# TOD.net
KiCad netlist of a schematic drawn in Altium Designer
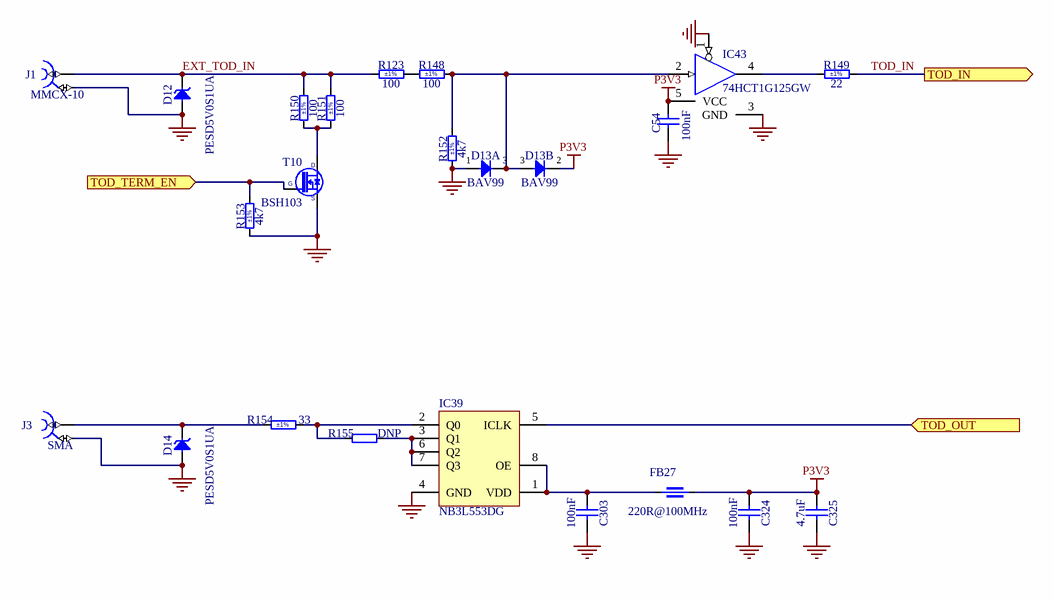
[diagram p0: TOD.SchDoc]

(export (version "E")
  (design (tool "Eeschema 10.0.6"))
  (components
    (comp (ref "C54")
      (value "100nF")
      (footprint "CAPC0603X33N")
      (description "Non-polarised capacitor")
      (fields
        (field (name "PART NUMBER") "CC0201_100NF_6.3V_10%_X5R")
        (field (name "VOLTAGE") "6.3V")
        (field (name "AUTHOR") "CERN DEM JLC")
      )
      (libsource (lib "Capacitors") (part "Capacitor - non polarized"))
    )
    (comp (ref "C303")
      (value "100nF")
      (footprint "CAPC0603X33N")
      (description "Non-polarised capacitor")
      (fields
        (field (name "PART NUMBER") "CC0201_100NF_6.3V_10%_X5R")
        (field (name "VOLTAGE") "6.3V")
        (field (name "AUTHOR") "CERN DEM JLC")
      )
      (libsource (lib "Capacitors") (part "Capacitor - non polarized"))
    )
    (comp (ref "C324")
      (value "100nF")
      (footprint "CAPC0603X33N")
      (description "Non-polarised capacitor")
      (fields
        (field (name "PART NUMBER") "CC0201_100NF_6.3V_10%_X5R")
        (field (name "VOLTAGE") "6.3V")
        (field (name "AUTHOR") "CERN DEM JLC")
      )
      (libsource (lib "Capacitors") (part "Capacitor - non polarized"))
    )
    (comp (ref "C325")
      (value "4.7uF")
      (footprint "CAPC1005X55N")
      (description "Non-polarised capacitor")
      (fields
        (field (name "PART NUMBER") "CC0402_4.7UF_6.3V_20%_X5R")
        (field (name "VOLTAGE") "6.3V")
        (field (name "AUTHOR") "CERN DEM JLC")
      )
      (libsource (lib "Capacitors") (part "Capacitor - non polarized"))
    )
    (comp (ref "D12")
      (value "PESD5V0S1UA")
      (footprint "SOD2512X110N")
      (description "Transient Voltage Suppressor Diode (Uni-Directional)")
      (fields
        (field (name "VOLTAGE") "5V")
        (field (name "POWER") "890W")
        (field (name "AUTHOR") "CERN DEM JLC")
      )
      (libsource (lib "ICs And Semiconductors") (part "Diode TVS Uni-Directional"))
    )
    (comp (ref "D13")
      (value "BAV99")
      (footprint "SOT95P240X110-3N")
      (description "Serial Diode")
      (fields
        (field (name "VOLTAGE") "70V")
        (field (name "POWER") "350mW")
        (field (name "AUTHOR") "CERN DEM JLC")
      )
      (libsource (lib "ICs And Semiconductors") (part "Diode x2 A1C3_A3C2"))
    )
    (comp (ref "D14")
      (value "PESD5V0S1UA")
      (footprint "SOD2512X110N")
      (description "Transient Voltage Suppressor Diode (Uni-Directional)")
      (fields
        (field (name "VOLTAGE") "5V")
        (field (name "POWER") "890W")
        (field (name "AUTHOR") "CERN DEM JLC")
      )
      (libsource (lib "ICs And Semiconductors") (part "Diode TVS Uni-Directional"))
    )
    (comp (ref "FB27")
      (value "220R@100MHz")
      (footprint "INDC1608X95N")
      (fields
        (field (name "TOLERANCE") "±25%")
        (field (name "PART NUMBER") "IND0603_MURATA_BLM18SG221TN1")
        (field (name "POWER") "2.5A")
        (field (name "AUTHOR") "CERN DEM MR")
      )
      (libsource (lib "Inductors & Transformers") (part "Ferrite Bead"))
    )
    (comp (ref "IC39")
      (value "NB3L553DG")
      (footprint "SOIC127P600X175-8N")
      (libsource (lib "MGlib") (part "NB3L553DG"))
    )
    (comp (ref "IC43")
      (value "74HCT1G125GW")
      (footprint "SOT65P210X110-5N")
      (description "Single Bus Buffer Gate With 3-State Output")
      (fields (field (name "MANUFACTURER") "NEXPERIA") (field (name "AUTHOR") "CERN DEM JMW"))
      (libsource (lib "ICs And Semiconductors") (part "741G125"))
    )
    (comp (ref "J1")
      (value "MMCX-10")
      (footprint "SAMTEC_MMCX-J-P-H-ST-TH1")
      (fields (field (name "AUTHOR") "CERN DEM JLC"))
      (libsource (lib "Connectors") (part "Coax_1Female_1Shield"))
    )
    (comp (ref "J3")
      (value "SMA")
      (footprint "DELOCK_65848")
      (description "50 Ohm Through Hole SMA Right Angle PCB Jack")
      (fields
        (field (name "PART NUMBER") "DELOCK_65848")
        (field (name "MANUFACTURER") "DELOCK")
        (field (name "AUTHOR") "GK")
      )
      (libsource (lib "Connectors") (part "CON_SMA_DELOCK_65848"))
    )
    (comp (ref "R123")
      (value "100")
      (footprint "RESC1005X40N")
      (description "Resistor - 1%")
      (fields
        (field (name "TOLERANCE") "±1%")
        (field (name "PART NUMBER") "R0402_100R_1%_0.0625W_100PPM")
        (field (name "POWER") "0.0625W")
        (field (name "AUTHOR") "CERN DEM JLC")
      )
      (libsource (lib "Resistors") (part "Resistor - 1%"))
    )
    (comp (ref "R148")
      (value "100")
      (footprint "RESC1005X40N")
      (description "Resistor - 1%")
      (fields
        (field (name "TOLERANCE") "±1%")
        (field (name "PART NUMBER") "R0402_100R_1%_0.0625W_100PPM")
        (field (name "POWER") "0.0625W")
        (field (name "AUTHOR") "CERN DEM JLC")
      )
      (libsource (lib "Resistors") (part "Resistor - 1%"))
    )
    (comp (ref "R149")
      (value "22")
      (footprint "RESC1005X40N")
      (description "Resistor - 1%")
      (fields
        (field (name "TOLERANCE") "±1%")
        (field (name "PART NUMBER") "R0402_22R_1%_0.0625W_100PPM")
        (field (name "POWER") "0.0625W")
        (field (name "AUTHOR") "CERN DEM JLC")
      )
      (libsource (lib "Resistors") (part "Resistor - 1%"))
    )
    (comp (ref "R150")
      (value "100")
      (footprint "RESC1005X40N")
      (description "Resistor - 1%")
      (fields
        (field (name "TOLERANCE") "±1%")
        (field (name "PART NUMBER") "R0402_100R_1%_0.0625W_100PPM")
        (field (name "POWER") "0.0625W")
        (field (name "AUTHOR") "CERN DEM JLC")
      )
      (libsource (lib "Resistors") (part "Resistor - 1%"))
    )
    (comp (ref "R151")
      (value "100")
      (footprint "RESC1005X40N")
      (description "Resistor - 1%")
      (fields
        (field (name "TOLERANCE") "±1%")
        (field (name "PART NUMBER") "R0402_100R_1%_0.0625W_100PPM")
        (field (name "POWER") "0.0625W")
        (field (name "AUTHOR") "CERN DEM JLC")
      )
      (libsource (lib "Resistors") (part "Resistor - 1%"))
    )
    (comp (ref "R152")
      (value "4k7")
      (footprint "RESC1005X40N")
      (description "Resistor - 1%")
      (fields
        (field (name "TOLERANCE") "±1%")
        (field (name "PART NUMBER") "R0402_4K7_1%_0.0625W_100PPM")
        (field (name "POWER") "0.0625W")
        (field (name "AUTHOR") "CERN DEM JLC")
      )
      (libsource (lib "Resistors") (part "Resistor - 1%"))
    )
    (comp (ref "R153")
      (value "4k7")
      (footprint "RESC1005X40N")
      (description "Resistor - 1%")
      (fields
        (field (name "TOLERANCE") "±1%")
        (field (name "PART NUMBER") "R0402_4K7_1%_0.0625W_100PPM")
        (field (name "POWER") "0.0625W")
        (field (name "AUTHOR") "CERN DEM JLC")
      )
      (libsource (lib "Resistors") (part "Resistor - 1%"))
    )
    (comp (ref "R154")
      (value "33")
      (footprint "RESC2012X60N")
      (description "Resistor - 1%")
      (fields
        (field (name "PART NUMBER") "R0805_33R_1%_0.125W_100PPM")
        (field (name "MANUFACTURER") "GENERIC")
        (field (name "TOLERANCE") "±1%")
        (field (name "AUTHOR") "CERN DEM JLC")
      )
      (libsource (lib "Resistors") (part "Resistor - 1%"))
    )
    (comp (ref "R155")
      (value "DNP")
      (footprint "RESC1005X40N")
      (description "Resistor")
      (fields
        (field (name "PART NUMBER") "R0402_0R_JUMPER")
        (field (name "MANUFACTURER") "GENERIC")
        (field (name "AUTHOR") "CERN DEM JLC")
      )
      (libsource (lib "Resistors") (part "Resistor"))
    )
    (comp (ref "T10")
      (value "BSH103")
      (footprint "SOT95P230X110-3N")
      (description "N-CHANNEL MOSFET WITH DIODE")
      (fields (field (name "MANUFACTURER") "NEXPERIA") (field (name "AUTHOR") "CERN DEM JLC"))
      (libsource (lib "ICs And Semiconductors") (part "N-MOSFET-D 1G 2S 3D"))
    )
  )
  (nets
    (net (code "1") (name "/EXT_TOD_IN") (class "Default")
      (node (ref "D12") (pin "1") (pinfunction "C_1") (pintype "passive"))
      (node (ref "J1") (pin "1") (pinfunction "1_1") (pintype "bidirectional"))
      (node (ref "R123") (pin "1") (pinfunction "1_1") (pintype "passive"))
      (node (ref "R150") (pin "2") (pinfunction "2_2") (pintype "passive"))
      (node (ref "R151") (pin "2") (pinfunction "2_2") (pintype "passive"))
    )
    (net (code "2") (name "/TOD_IN") (class "Default")
      (node (ref "R149") (pin "2") (pinfunction "2_2") (pintype "passive"))
    )
    (net (code "3") (name "/TOD_OUT") (class "Default")
      (node (ref "IC39") (pin "5") (pinfunction "ICLK_5") (pintype "passive"))
    )
    (net (code "4") (name "/TOD_TERM_EN") (class "Default")
      (node (ref "R153") (pin "2") (pinfunction "2_2") (pintype "passive"))
      (node (ref "T10") (pin "1") (pinfunction "G_1") (pintype "passive"))
    )
    (net (code "5") (name "GND") (class "Default")
      (node (ref "C303") (pin "1") (pinfunction "1_1") (pintype "passive"))
      (node (ref "C324") (pin "1") (pinfunction "1_1") (pintype "passive"))
      (node (ref "C325") (pin "1") (pinfunction "1_1") (pintype "passive"))
      (node (ref "C54") (pin "1") (pinfunction "1_1") (pintype "passive"))
      (node (ref "D12") (pin "2") (pinfunction "A_2") (pintype "passive"))
      (node (ref "D13") (pin "1") (pinfunction "A_1") (pintype "passive"))
      (node (ref "D14") (pin "2") (pinfunction "A_2") (pintype "passive"))
      (node (ref "IC39") (pin "4") (pinfunction "GND_4") (pintype "passive"))
      (node (ref "IC43") (pin "1") (pinfunction "~{G}_1") (pintype "input"))
      (node (ref "IC43") (pin "3") (pinfunction "GND_3") (pintype "power_in"))
      (node (ref "J1") (pin "2") (pinfunction "2_2") (pintype "bidirectional"))
      (node (ref "J3") (pin "2") (pinfunction "2_2") (pintype "bidirectional"))
      (node (ref "R152") (pin "1") (pinfunction "1_1") (pintype "passive"))
      (node (ref "R153") (pin "1") (pinfunction "1_1") (pintype "passive"))
      (node (ref "T10") (pin "2") (pinfunction "S_2") (pintype "passive"))
    )
    (net (code "6") (name "Net-(D13A-COMAC)") (class "Default")
      (node (ref "D13") (pin "3") (pinfunction "COMAC_3") (pintype "passive"))
      (node (ref "IC43") (pin "2") (pinfunction "IN_2") (pintype "input"))
      (node (ref "R148") (pin "2") (pinfunction "2_2") (pintype "passive"))
      (node (ref "R152") (pin "2") (pinfunction "2_2") (pintype "passive"))
    )
    (net (code "7") (name "Net-(D14-C)") (class "Default")
      (node (ref "D14") (pin "1") (pinfunction "C_1") (pintype "passive"))
      (node (ref "J3") (pin "1") (pinfunction "1_1") (pintype "bidirectional"))
      (node (ref "R154") (pin "1") (pinfunction "1_1") (pintype "passive"))
    )
    (net (code "8") (name "Net-(IC39-OE)") (class "Default")
      (node (ref "C303") (pin "2") (pinfunction "2_2") (pintype "passive"))
      (node (ref "FB27") (pin "2") (pinfunction "2_2") (pintype "passive"))
      (node (ref "IC39") (pin "1") (pinfunction "VDD_1") (pintype "passive"))
      (node (ref "IC39") (pin "8") (pinfunction "OE_8") (pintype "passive"))
    )
    (net (code "9") (name "Net-(IC39-Q0)") (class "Default")
      (node (ref "IC39") (pin "2") (pinfunction "Q0_2") (pintype "passive"))
      (node (ref "R154") (pin "2") (pinfunction "2_2") (pintype "passive"))
      (node (ref "R155") (pin "1") (pinfunction "1_1") (pintype "passive"))
    )
    (net (code "10") (name "Net-(IC39-Q1)") (class "Default")
      (node (ref "IC39") (pin "3") (pinfunction "Q1_3") (pintype "passive"))
      (node (ref "IC39") (pin "6") (pinfunction "Q2_6") (pintype "passive"))
      (node (ref "IC39") (pin "7") (pinfunction "Q3_7") (pintype "passive"))
      (node (ref "R155") (pin "2") (pinfunction "2_2") (pintype "passive"))
    )
    (net (code "11") (name "Net-(IC43-OUT)") (class "Default")
      (node (ref "IC43") (pin "4") (pinfunction "OUT_4") (pintype "tri_state"))
      (node (ref "R149") (pin "1") (pinfunction "1_1") (pintype "passive"))
    )
    (net (code "12") (name "Net-(R123-Pad2)") (class "Default")
      (node (ref "R123") (pin "2") (pinfunction "2_2") (pintype "passive"))
      (node (ref "R148") (pin "1") (pinfunction "1_1") (pintype "passive"))
    )
    (net (code "13") (name "Net-(T10-D)") (class "Default")
      (node (ref "R150") (pin "1") (pinfunction "1_1") (pintype "passive"))
      (node (ref "R151") (pin "1") (pinfunction "1_1") (pintype "passive"))
      (node (ref "T10") (pin "3") (pinfunction "D_3") (pintype "passive"))
    )
    (net (code "14") (name "P3V3") (class "Default")
      (node (ref "C324") (pin "2") (pinfunction "2_2") (pintype "passive"))
      (node (ref "C325") (pin "2") (pinfunction "2_2") (pintype "passive"))
      (node (ref "C54") (pin "2") (pinfunction "2_2") (pintype "passive"))
      (node (ref "D13") (pin "2") (pinfunction "C_2") (pintype "passive"))
      (node (ref "FB27") (pin "1") (pinfunction "1_1") (pintype "passive"))
      (node (ref "IC43") (pin "5") (pinfunction "VCC_5") (pintype "power_in"))
    )
  )
)
